# SCH_oscilliscope_copy_2021-08-04.net
KiCad netlist of a schematic drawn in EasyEDA
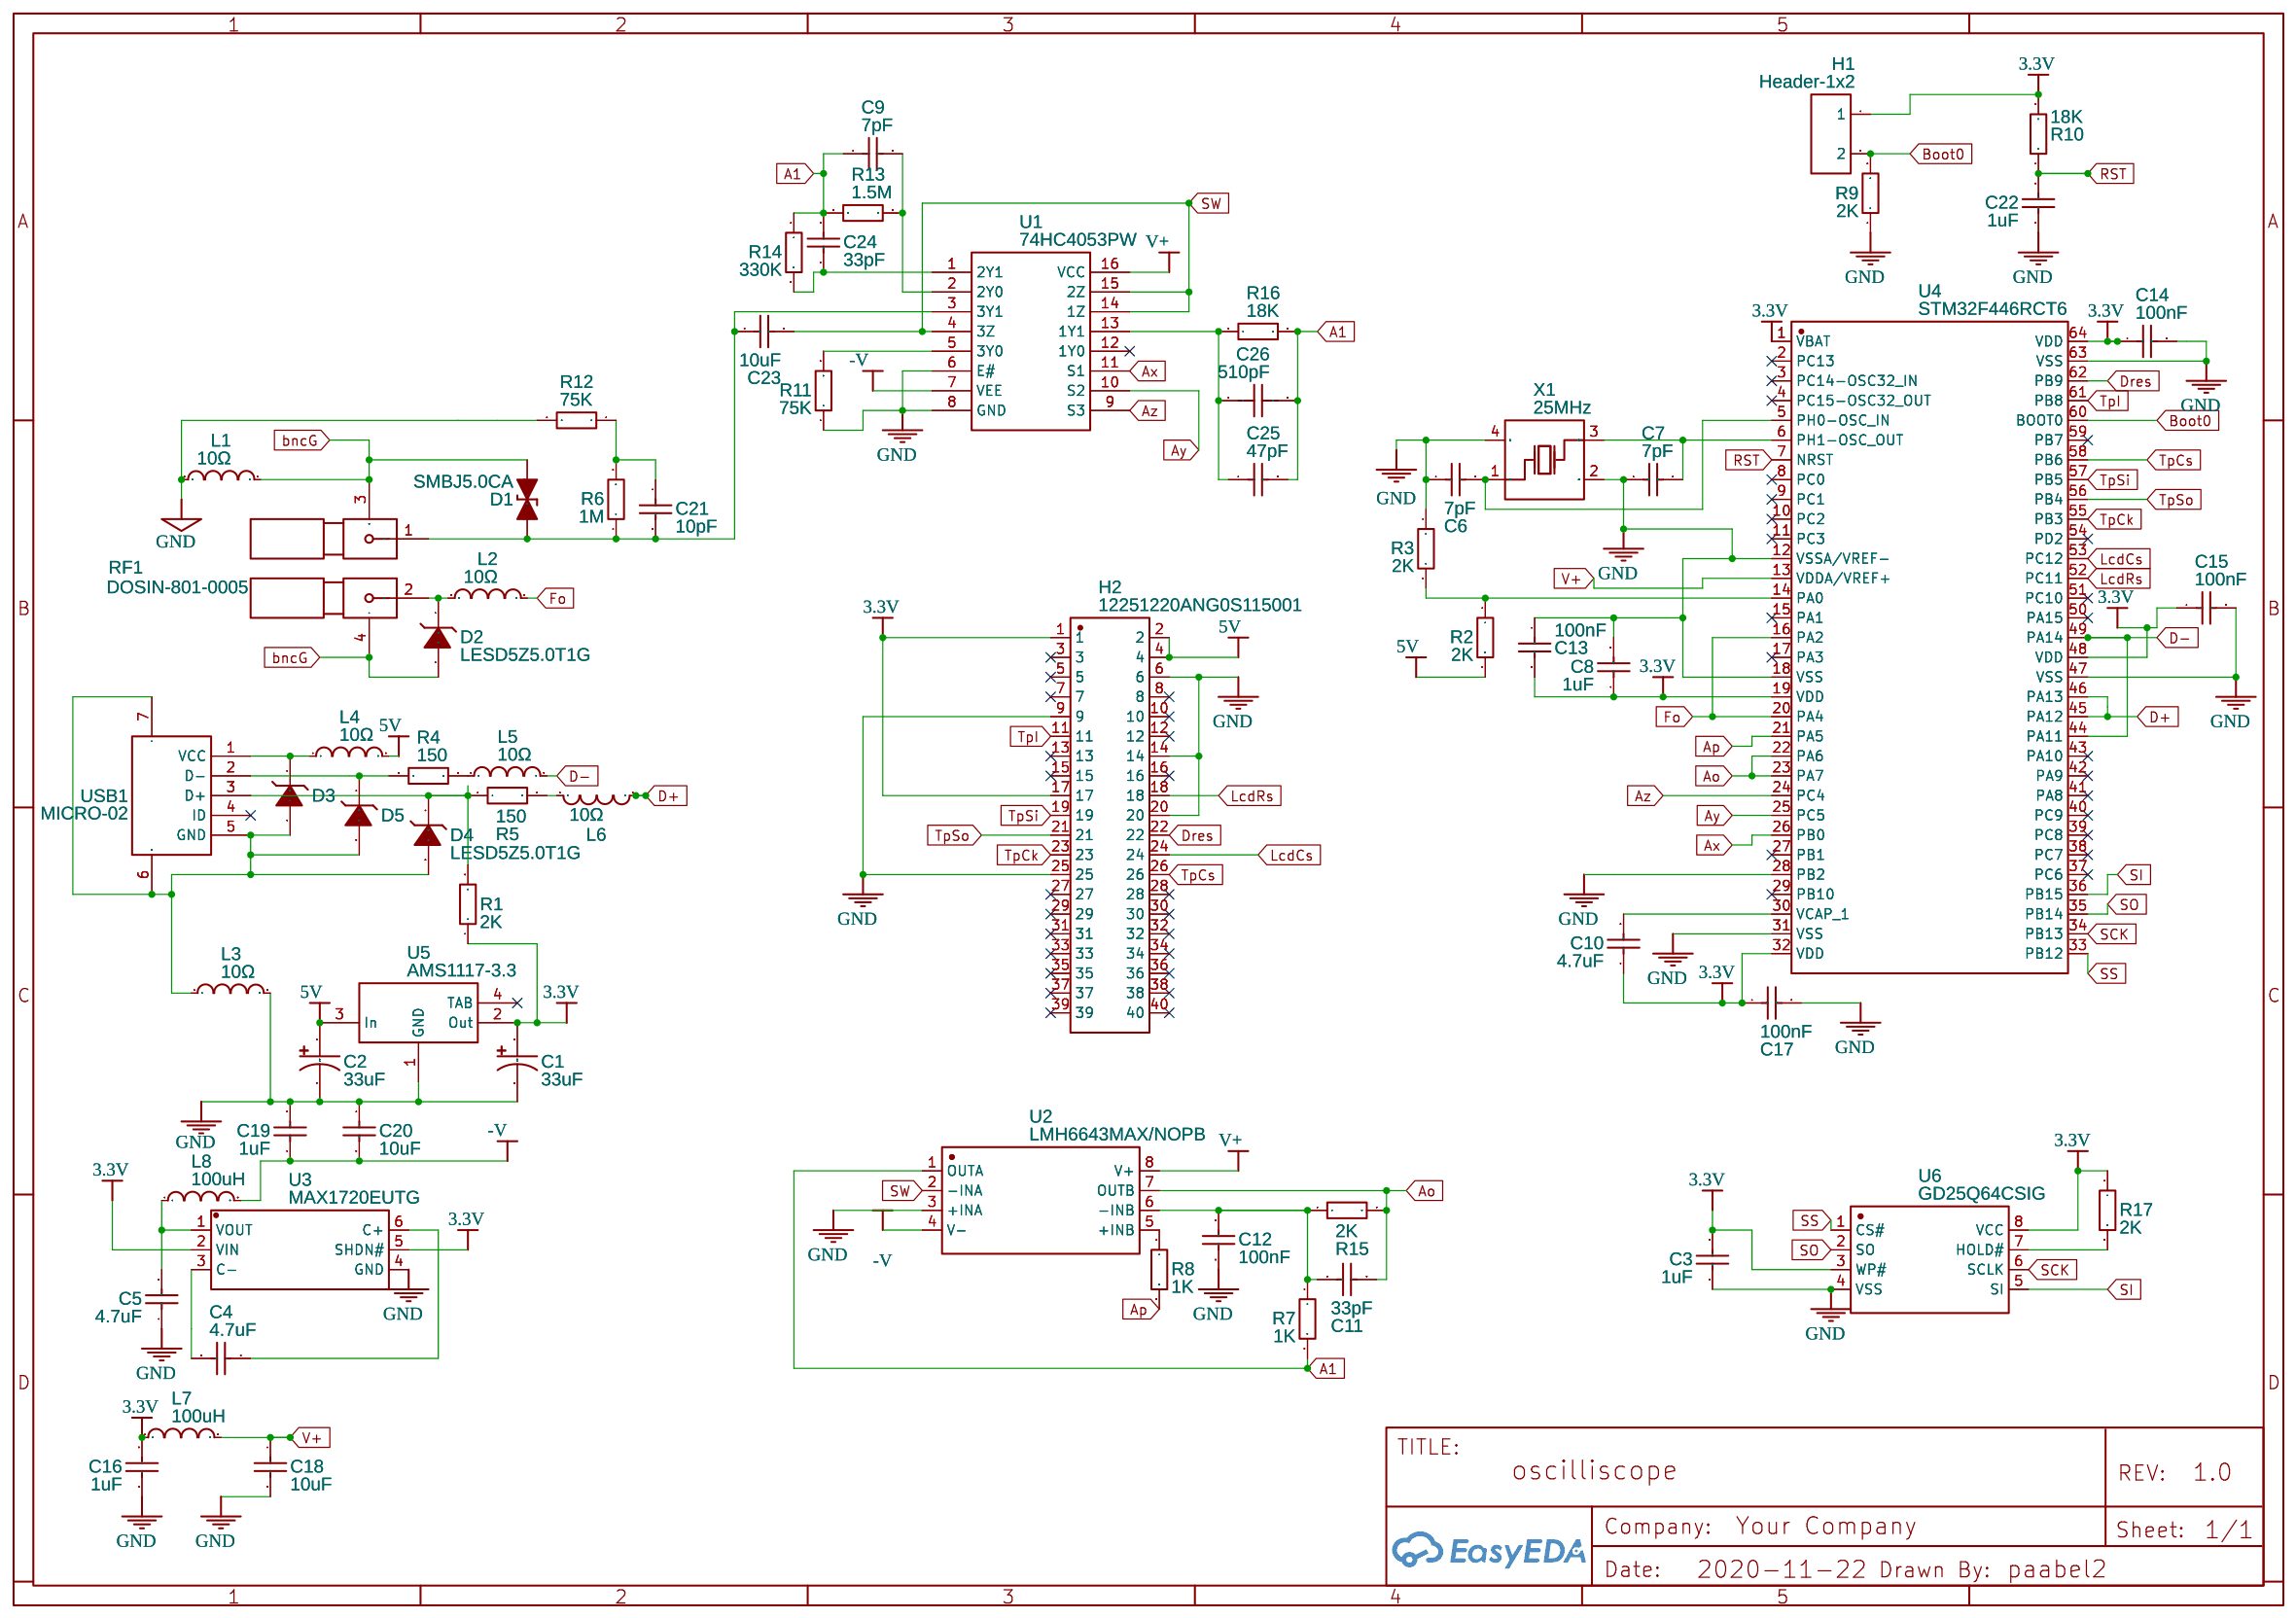
[diagram p0: schematic sheet]

(export (version "E")
  (design (tool "Eeschema 10.0.6"))
  (components
    (comp (ref "C1")
      (value "33uF")
      (fields
        (field (name "BOM_Manufacturer Part") "TC211A336M006Y")
        (field (name "BOM_Supplier Part") "C128344")
      )
      (libsource (lib "") (part "TC211A336M006Y"))
    )
    (comp (ref "C2")
      (value "33uF")
      (fields
        (field (name "BOM_Manufacturer Part") "TC211A336M006Y")
        (field (name "BOM_Supplier Part") "C128344")
      )
      (libsource (lib "") (part "TC211A336M006Y"))
    )
    (comp (ref "C3")
      (value "1uF")
      (fields
        (field (name "BOM_Manufacturer Part") "CL05A105KP5NNNC")
        (field (name "BOM_Supplier Part") "C14445")
      )
      (libsource (lib "") (part "CL05A105KP5NNNC"))
    )
    (comp (ref "C4")
      (value "4.7uF")
      (fields
        (field (name "BOM_Manufacturer Part") "CL21A475KAQNNNE")
        (field (name "BOM_Supplier Part") "C1779")
      )
      (libsource (lib "") (part "CL21A475KAQNNNE_1"))
    )
    (comp (ref "C5")
      (value "4.7uF")
      (fields
        (field (name "BOM_Manufacturer Part") "CL21A475KAQNNNE")
        (field (name "BOM_Supplier Part") "C1779")
      )
      (libsource (lib "") (part "CL21A475KAQNNNE"))
    )
    (comp (ref "C6")
      (value "7pF")
      (fields
        (field (name "BOM_Manufacturer Part") "0402CG7R0C500NT")
        (field (name "BOM_Supplier Part") "C1577")
      )
      (libsource (lib "") (part "0402CG7R0C500NT_1"))
    )
    (comp (ref "C7")
      (value "7pF")
      (fields
        (field (name "BOM_Manufacturer Part") "0402CG7R0C500NT")
        (field (name "BOM_Supplier Part") "C1577")
      )
      (libsource (lib "") (part "0402CG7R0C500NT"))
    )
    (comp (ref "C8")
      (value "1uF")
      (fields
        (field (name "BOM_Manufacturer Part") "CL05A105KP5NNNC")
        (field (name "BOM_Supplier Part") "C14445")
      )
      (libsource (lib "") (part "CL05A105KP5NNNC"))
    )
    (comp (ref "C9")
      (value "7pF")
      (fields
        (field (name "BOM_Manufacturer Part") "0402CG7R0C500NT")
        (field (name "BOM_Supplier Part") "C1577")
      )
      (libsource (lib "") (part "0402CG7R0C500NT"))
    )
    (comp (ref "C10")
      (value "4.7uF")
      (fields
        (field (name "BOM_Manufacturer Part") "CL21A475KAQNNNE")
        (field (name "BOM_Supplier Part") "C1779")
      )
      (libsource (lib "") (part "CL21A475KAQNNNE"))
    )
    (comp (ref "C11")
      (value "33pF")
      (fields
        (field (name "BOM_Manufacturer Part") "0402CG330J500NT")
        (field (name "BOM_Supplier Part") "C1562")
      )
      (libsource (lib "") (part "0402CG330J500NT"))
    )
    (comp (ref "C12")
      (value "100nF")
      (fields
        (field (name "BOM_Manufacturer Part") "CL05B104KO5NNNC")
        (field (name "BOM_Supplier Part") "C1525")
      )
      (libsource (lib "") (part "CL05B104KO5NNNC_1"))
    )
    (comp (ref "C13")
      (value "100nF")
      (fields
        (field (name "BOM_Manufacturer Part") "CL05B104KO5NNNC")
        (field (name "BOM_Supplier Part") "C1525")
      )
      (libsource (lib "") (part "CL05B104KO5NNNC_2"))
    )
    (comp (ref "C14")
      (value "100nF")
      (fields
        (field (name "BOM_Manufacturer Part") "CL05B104KO5NNNC")
        (field (name "BOM_Supplier Part") "C1525")
      )
      (libsource (lib "") (part "CL05B104KO5NNNC"))
    )
    (comp (ref "C15")
      (value "100nF")
      (fields
        (field (name "BOM_Manufacturer Part") "CL05B104KO5NNNC")
        (field (name "BOM_Supplier Part") "C1525")
      )
      (libsource (lib "") (part "CL05B104KO5NNNC"))
    )
    (comp (ref "C16")
      (value "1uF")
      (fields
        (field (name "BOM_Manufacturer Part") "CL05A105KP5NNNC")
        (field (name "BOM_Supplier Part") "C14445")
      )
      (libsource (lib "") (part "CL05A105KP5NNNC"))
    )
    (comp (ref "C17")
      (value "100nF")
      (fields
        (field (name "BOM_Manufacturer Part") "CL05B104KO5NNNC")
        (field (name "BOM_Supplier Part") "C1525")
      )
      (libsource (lib "") (part "CL05B104KO5NNNC_3"))
    )
    (comp (ref "C18")
      (value "10uF")
      (fields
        (field (name "BOM_Manufacturer Part") "CL21A106KAYNNNE")
        (field (name "BOM_Supplier Part") "C15850")
      )
      (libsource (lib "") (part "CL21A106KAYNNNE_1"))
    )
    (comp (ref "C19")
      (value "1uF")
      (fields
        (field (name "BOM_Manufacturer Part") "CL05A105KP5NNNC")
        (field (name "BOM_Supplier Part") "C14445")
      )
      (libsource (lib "") (part "CL05A105KP5NNNC"))
    )
    (comp (ref "C20")
      (value "10uF")
      (fields
        (field (name "BOM_Manufacturer Part") "CL21A106KAYNNNE")
        (field (name "BOM_Supplier Part") "C15850")
      )
      (libsource (lib "") (part "CL21A106KAYNNNE_1"))
    )
    (comp (ref "C21")
      (value "10pF")
      (fields
        (field (name "BOM_Manufacturer Part") "CL10C100JB8NNNC")
        (field (name "BOM_Supplier Part") "C1634")
      )
      (libsource (lib "") (part "CL10C100JB8NNNC"))
    )
    (comp (ref "C22")
      (value "1uF")
      (fields
        (field (name "BOM_Manufacturer Part") "CL05A105KP5NNNC")
        (field (name "BOM_Supplier Part") "C14445")
      )
      (libsource (lib "") (part "CL05A105KP5NNNC"))
    )
    (comp (ref "C23")
      (value "10uF")
      (fields
        (field (name "BOM_Manufacturer Part") "CL21A106KAYNNNE")
        (field (name "BOM_Supplier Part") "C15850")
      )
      (libsource (lib "") (part "CL21A106KAYNNNE"))
    )
    (comp (ref "C24")
      (value "33pF")
      (fields
        (field (name "BOM_Manufacturer Part") "0402CG330J500NT")
        (field (name "BOM_Supplier Part") "C1562")
      )
      (libsource (lib "") (part "0402CG330J500NT_1"))
    )
    (comp (ref "C25")
      (value "47pF")
      (fields
        (field (name "BOM_Manufacturer Part") "CL10C470JB8NNNC")
        (field (name "BOM_Supplier Part") "C1671")
      )
      (libsource (lib "") (part "CL10C470JB8NNNC"))
    )
    (comp (ref "C26")
      (value "510pF")
      (fields
        (field (name "BOM_Manufacturer Part") "CL10B511KB8NNNC")
        (field (name "BOM_Supplier Part") "C170144")
      )
      (libsource (lib "") (part "CL10B511KB8NNNC"))
    )
    (comp (ref "D1")
      (value "SMBJ5.0CA")
      (fields (field (name "BOM_Supplier Part") "C78424"))
      (libsource (lib "") (part "SMBJ5.0CA-C78424"))
    )
    (comp (ref "D2")
      (value "LESD5Z5.0T1G")
      (fields (field (name "BOM_Supplier Part") "C136171"))
      (libsource (lib "") (part "LESD5Z5.0T1G"))
    )
    (comp (ref "D3")
      (value "LESD5Z5.0T1G")
      (fields (field (name "BOM_Supplier Part") "C136171"))
      (libsource (lib "") (part "LESD5Z5.0T1G"))
    )
    (comp (ref "D4")
      (value "LESD5Z5.0T1G")
      (fields (field (name "BOM_Supplier Part") "C136171"))
      (libsource (lib "") (part "LESD5Z5.0T1G"))
    )
    (comp (ref "D5")
      (value "LESD5Z5.0T1G")
      (fields (field (name "BOM_Supplier Part") "C136171"))
      (libsource (lib "") (part "LESD5Z5.0T1G"))
    )
    (comp (ref "H1")
      (value "Header-1x2")
      (fields (field (name "BOM_Manufacturer Part") "826629-2") (field (name "BOM_Supplier Part") "C86471"))
      (libsource (lib "") (part "Header-Male-2.54_1x2"))
    )
    (comp (ref "H2")
      (value "12251220ANG0S115001")
      (fields (field (name "BOM_Supplier Part") "C429965"))
      (libsource (lib "") (part "12251220ANG0S115001"))
    )
    (comp (ref "L1")
      (value "10Ω")
      (fields
        (field (name "BOM_Manufacturer Part") "BLM15AG100SN1D")
        (field (name "BOM_Supplier Part") "C76882")
      )
      (libsource (lib "") (part "BLM15AG100SN1D_1"))
    )
    (comp (ref "L2")
      (value "10Ω")
      (fields
        (field (name "BOM_Manufacturer Part") "BLM15AG100SN1D")
        (field (name "BOM_Supplier Part") "C76882")
      )
      (libsource (lib "") (part "BLM15AG100SN1D_3"))
    )
    (comp (ref "L3")
      (value "10Ω")
      (fields
        (field (name "BOM_Manufacturer Part") "BLM15AG100SN1D")
        (field (name "BOM_Supplier Part") "C76882")
      )
      (libsource (lib "") (part "BLM15AG100SN1D_4"))
    )
    (comp (ref "L4")
      (value "10Ω")
      (fields
        (field (name "BOM_Manufacturer Part") "BLM15AG100SN1D")
        (field (name "BOM_Supplier Part") "C76882")
      )
      (libsource (lib "") (part "BLM15AG100SN1D_2"))
    )
    (comp (ref "L5")
      (value "10Ω")
      (fields
        (field (name "BOM_Manufacturer Part") "BLM15AG100SN1D")
        (field (name "BOM_Supplier Part") "C76882")
      )
      (libsource (lib "") (part "BLM15AG100SN1D_2"))
    )
    (comp (ref "L6")
      (value "10Ω")
      (fields
        (field (name "BOM_Manufacturer Part") "BLM15AG100SN1D")
        (field (name "BOM_Supplier Part") "C76882")
      )
      (libsource (lib "") (part "BLM15AG100SN1D"))
    )
    (comp (ref "L7")
      (value "100uH")
      (fields
        (field (name "BOM_Manufacturer Part") "SCCD32-101KT")
        (field (name "BOM_Supplier Part") "C532859")
      )
      (libsource (lib "") (part "SCCD32-101KT"))
    )
    (comp (ref "L8")
      (value "100uH")
      (fields
        (field (name "BOM_Manufacturer Part") "SCCD32-101KT")
        (field (name "BOM_Supplier Part") "C532859")
      )
      (libsource (lib "") (part "SCCD32-101KT"))
    )
    (comp (ref "R1")
      (value "2K")
      (fields
        (field (name "BOM_Manufacturer Part") "0603WAF2001T5E")
        (field (name "BOM_Supplier Part") "C22975")
      )
      (libsource (lib "") (part "0603WAF2001T5E_2"))
    )
    (comp (ref "R2")
      (value "2K")
      (fields
        (field (name "BOM_Manufacturer Part") "0603WAF2001T5E")
        (field (name "BOM_Supplier Part") "C22975")
      )
      (libsource (lib "") (part "0603WAF2001T5E_1"))
    )
    (comp (ref "R3")
      (value "2K")
      (fields
        (field (name "BOM_Manufacturer Part") "0603WAF2001T5E")
        (field (name "BOM_Supplier Part") "C22975")
      )
      (libsource (lib "") (part "0603WAF2001T5E_1"))
    )
    (comp (ref "R4")
      (value "150")
      (fields
        (field (name "BOM_Manufacturer Part") "0603WAF1500T5E")
        (field (name "BOM_Supplier Part") "C22808")
      )
      (libsource (lib "") (part "0603WAF1500T5E"))
    )
    (comp (ref "R5")
      (value "150")
      (fields
        (field (name "BOM_Manufacturer Part") "0603WAF1500T5E")
        (field (name "BOM_Supplier Part") "C22808")
      )
      (libsource (lib "") (part "0603WAF1500T5E"))
    )
    (comp (ref "R6")
      (value "1M")
      (fields
        (field (name "BOM_Manufacturer Part") "0603WAF1004T5E")
        (field (name "BOM_Supplier Part") "C22935")
      )
      (libsource (lib "") (part "0603WAF1004T5E"))
    )
    (comp (ref "R7")
      (value "1K")
      (fields
        (field (name "BOM_Manufacturer Part") "0603WAF1001T5E")
        (field (name "BOM_Supplier Part") "C21190")
      )
      (libsource (lib "") (part "0603WAF1001T5E"))
    )
    (comp (ref "R8")
      (value "1K")
      (fields
        (field (name "BOM_Manufacturer Part") "0603WAF1001T5E")
        (field (name "BOM_Supplier Part") "C21190")
      )
      (libsource (lib "") (part "0603WAF1001T5E"))
    )
    (comp (ref "R9")
      (value "2K")
      (fields
        (field (name "BOM_Manufacturer Part") "0603WAF2001T5E")
        (field (name "BOM_Supplier Part") "C22975")
      )
      (libsource (lib "") (part "0603WAF2001T5E_2"))
    )
    (comp (ref "R10")
      (value "18K")
      (fields
        (field (name "BOM_Manufacturer Part") "0603WAF1802T5E")
        (field (name "BOM_Supplier Part") "C25810")
      )
      (libsource (lib "") (part "0603WAF1802T5E"))
    )
    (comp (ref "R11")
      (value "75K")
      (fields
        (field (name "BOM_Manufacturer Part") "0603WAF7502T5E")
        (field (name "BOM_Supplier Part") "C23242")
      )
      (libsource (lib "") (part "0603WAF7502T5E"))
    )
    (comp (ref "R12")
      (value "75K")
      (fields
        (field (name "BOM_Manufacturer Part") "0603WAF7502T5E")
        (field (name "BOM_Supplier Part") "C23242")
      )
      (libsource (lib "") (part "0603WAF7502T5E_1"))
    )
    (comp (ref "R13")
      (value "1.5M")
      (fields
        (field (name "BOM_Manufacturer Part") "0603WAF1504T5E")
        (field (name "BOM_Supplier Part") "C4172")
      )
      (libsource (lib "") (part "0603WAF1504T5E"))
    )
    (comp (ref "R14")
      (value "330K")
      (fields
        (field (name "BOM_Manufacturer Part") "RTT03334JTP")
        (field (name "BOM_Supplier Part") "C103555")
      )
      (libsource (lib "") (part "RTT03334JTP"))
    )
    (comp (ref "R15")
      (value "2K")
      (fields
        (field (name "BOM_Manufacturer Part") "0603WAF2001T5E")
        (field (name "BOM_Supplier Part") "C22975")
      )
      (libsource (lib "") (part "0603WAF2001T5E"))
    )
    (comp (ref "R16")
      (value "18K")
      (fields
        (field (name "BOM_Manufacturer Part") "0603WAF1802T5E")
        (field (name "BOM_Supplier Part") "C25810")
      )
      (libsource (lib "") (part "0603WAF1802T5E_1"))
    )
    (comp (ref "R17")
      (value "2K")
      (fields
        (field (name "BOM_Manufacturer Part") "0603WAF2001T5E")
        (field (name "BOM_Supplier Part") "C22975")
      )
      (libsource (lib "") (part "0603WAF2001T5E_1"))
    )
    (comp (ref "RF1")
      (value "DOSIN-801-0005")
      (fields (field (name "BOM_Supplier Part") "C521213"))
      (libsource (lib "") (part "DOSIN-801-0005"))
    )
    (comp (ref "U1")
      (value "74HC4053PW")
      (fields (field (name "BOM_Supplier Part") "C5648"))
      (libsource (lib "") (part "74HC4053PW"))
    )
    (comp (ref "U2")
      (value "LMH6643MAX/NOPB")
      (fields (field (name "BOM_Supplier Part") "C44880"))
      (libsource (lib "") (part "LMH6643MAX/NOPB"))
    )
    (comp (ref "U3")
      (value "MAX1720EUTG")
      (fields (field (name "BOM_Supplier Part") "C70466"))
      (libsource (lib "") (part "MAX1720EUTG"))
    )
    (comp (ref "U4")
      (value "STM32F446RCT6")
      (fields (field (name "BOM_Supplier Part") "C1338449"))
      (libsource (lib "") (part "STM32F446RET6"))
    )
    (comp (ref "U5")
      (value "AMS1117-3.3")
      (fields (field (name "BOM_Supplier Part") "C165482"))
      (libsource (lib "") (part "AMS1117-3.3_C165482"))
    )
    (comp (ref "U6")
      (value "GD25Q64CSIG")
      (fields (field (name "BOM_Supplier Part") "C79076"))
      (libsource (lib "") (part "GD25Q64CSIG"))
    )
    (comp (ref "USB1")
      (value "MICRO-02")
      (fields
        (field (name "BOM_Manufacturer Part") "MICRO-02-G1P3-A1T2")
        (field (name "BOM_Supplier Part") "C2682518")
      )
      (libsource (lib "") (part "MICRO-02-G1P3-A1T2"))
    )
    (comp (ref "X1")
      (value "25MHz")
      (fields
        (field (name "BOM_Manufacturer Part") "X322525MOB4SI")
        (field (name "BOM_Supplier Part") "C9006")
      )
      (libsource (lib "") (part "X322525MOB4SI"))
    )
  )
  (nets
    (net (code "1") (name "-V") (class "Default")
      (node (ref "C19") (pin "1") (pinfunction "1_1") (pintype "input"))
      (node (ref "C20") (pin "2") (pinfunction "2_2") (pintype "input"))
      (node (ref "L8") (pin "2") (pinfunction "2_2") (pintype "unspecified"))
      (node (ref "U1") (pin "7") (pinfunction "VEE_7") (pintype "unspecified"))
      (node (ref "U2") (pin "4") (pinfunction "V-_4") (pintype "unspecified"))
    )
    (net (code "2") (name "3.3V") (class "Default")
      (node (ref "C1") (pin "1") (pinfunction "1_1") (pintype "unspecified"))
      (node (ref "C10") (pin "1") (pinfunction "1_1") (pintype "input"))
      (node (ref "C13") (pin "2") (pinfunction "2_2") (pintype "input"))
      (node (ref "C14") (pin "1") (pinfunction "1_1") (pintype "input"))
      (node (ref "C15") (pin "1") (pinfunction "1_1") (pintype "input"))
      (node (ref "C16") (pin "2") (pinfunction "2_2") (pintype "input"))
      (node (ref "C17") (pin "1") (pinfunction "1_1") (pintype "input"))
      (node (ref "C3") (pin "2") (pinfunction "2_2") (pintype "input"))
      (node (ref "C8") (pin "1") (pinfunction "1_1") (pintype "input"))
      (node (ref "H1") (pin "1") (pinfunction "1_1") (pintype "unspecified"))
      (node (ref "H2") (pin "1") (pinfunction "1_1") (pintype "unspecified"))
      (node (ref "H2") (pin "17") (pinfunction "17_17") (pintype "unspecified"))
      (node (ref "L7") (pin "1") (pinfunction "1_1") (pintype "unspecified"))
      (node (ref "R1") (pin "1") (pinfunction "1_1") (pintype "input"))
      (node (ref "R10") (pin "2") (pinfunction "2_2") (pintype "input"))
      (node (ref "R17") (pin "1") (pinfunction "1_1") (pintype "input"))
      (node (ref "U3") (pin "2") (pinfunction "VIN_2") (pintype "unspecified"))
      (node (ref "U3") (pin "5") (pinfunction "SHDN#_5") (pintype "unspecified"))
      (node (ref "U4") (pin "1") (pinfunction "VBAT_1") (pintype "unspecified"))
      (node (ref "U4") (pin "19") (pinfunction "VDD_19") (pintype "unspecified"))
      (node (ref "U4") (pin "32") (pinfunction "VDD_32") (pintype "unspecified"))
      (node (ref "U4") (pin "48") (pinfunction "VDD_48") (pintype "unspecified"))
      (node (ref "U4") (pin "64") (pinfunction "VDD_64") (pintype "unspecified"))
      (node (ref "U5") (pin "2") (pinfunction "Out_2") (pintype "unspecified"))
      (node (ref "U6") (pin "3") (pinfunction "WP#_3") (pintype "unspecified"))
      (node (ref "U6") (pin "8") (pinfunction "VCC_8") (pintype "unspecified"))
    )
    (net (code "3") (name "5V") (class "Default")
      (node (ref "C2") (pin "1") (pinfunction "1_1") (pintype "unspecified"))
      (node (ref "H2") (pin "2") (pinfunction "2_2") (pintype "unspecified"))
      (node (ref "H2") (pin "4") (pinfunction "4_4") (pintype "unspecified"))
      (node (ref "L4") (pin "2") (pinfunction "2_2") (pintype "unspecified"))
      (node (ref "R2") (pin "2") (pinfunction "2_2") (pintype "input"))
      (node (ref "U5") (pin "3") (pinfunction "In_3") (pintype "unspecified"))
    )
    (net (code "4") (name "A1") (class "Default")
      (node (ref "C24") (pin "2") (pinfunction "2_2") (pintype "input"))
      (node (ref "C25") (pin "2") (pinfunction "2_2") (pintype "input"))
      (node (ref "C26") (pin "2") (pinfunction "2_2") (pintype "unspecified"))
      (node (ref "C9") (pin "1") (pinfunction "1_1") (pintype "input"))
      (node (ref "R13") (pin "1") (pinfunction "1_1") (pintype "input"))
      (node (ref "R14") (pin "1") (pinfunction "1_1") (pintype "input"))
      (node (ref "R16") (pin "2") (pinfunction "2_2") (pintype "input"))
      (node (ref "R7") (pin "2") (pinfunction "2_2") (pintype "input"))
      (node (ref "U2") (pin "1") (pinfunction "OUTA_1") (pintype "unspecified"))
    )
    (net (code "5") (name "Ao") (class "Default")
      (node (ref "C11") (pin "2") (pinfunction "2_2") (pintype "input"))
      (node (ref "R15") (pin "2") (pinfunction "2_2") (pintype "input"))
      (node (ref "U2") (pin "7") (pinfunction "OUTB_7") (pintype "unspecified"))
      (node (ref "U4") (pin "22") (pinfunction "PA6_22") (pintype "unspecified"))
      (node (ref "U4") (pin "23") (pinfunction "PA7_23") (pintype "unspecified"))
    )
    (net (code "6") (name "Ap") (class "Default")
      (node (ref "R8") (pin "2") (pinfunction "2_2") (pintype "input"))
      (node (ref "U4") (pin "21") (pinfunction "PA5_21") (pintype "unspecified"))
    )
    (net (code "7") (name "Ax") (class "Default")
      (node (ref "U1") (pin "11") (pinfunction "S1_11") (pintype "unspecified"))
      (node (ref "U4") (pin "26") (pinfunction "PB0_26") (pintype "unspecified"))
    )
    (net (code "8") (name "Ay") (class "Default")
      (node (ref "U1") (pin "10") (pinfunction "S2_10") (pintype "unspecified"))
      (node (ref "U4") (pin "25") (pinfunction "PC5_25") (pintype "unspecified"))
    )
    (net (code "9") (name "Az") (class "Default")
      (node (ref "U1") (pin "9") (pinfunction "S3_9") (pintype "unspecified"))
      (node (ref "U4") (pin "24") (pinfunction "PC4_24") (pintype "unspecified"))
    )
    (net (code "10") (name "Boot0") (class "Default")
      (node (ref "H1") (pin "2") (pinfunction "2_2") (pintype "unspecified"))
      (node (ref "R9") (pin "2") (pinfunction "2_2") (pintype "input"))
      (node (ref "U4") (pin "60") (pinfunction "BOOT0_60") (pintype "unspecified"))
    )
    (net (code "11") (name "D+") (class "Default")
      (node (ref "L6") (pin "1") (pinfunction "1_1") (pintype "unspecified"))
      (node (ref "U4") (pin "45") (pinfunction "PA12_45") (pintype "unspecified"))
      (node (ref "U4") (pin "46") (pinfunction "PA13_46") (pintype "unspecified"))
    )
    (net (code "12") (name "D-") (class "Default")
      (node (ref "L5") (pin "2") (pinfunction "2_2") (pintype "unspecified"))
      (node (ref "U4") (pin "44") (pinfunction "PA11_44") (pintype "unspecified"))
      (node (ref "U4") (pin "49") (pinfunction "PA14_49") (pintype "unspecified"))
    )
    (net (code "13") (name "Dres") (class "Default")
      (node (ref "H2") (pin "22") (pinfunction "22_22") (pintype "unspecified"))
      (node (ref "U4") (pin "62") (pinfunction "PB9_62") (pintype "unspecified"))
    )
    (net (code "14") (name "Fo") (class "Default")
      (node (ref "L2") (pin "1") (pinfunction "1_1") (pintype "unspecified"))
      (node (ref "U4") (pin "16") (pinfunction "PA2_16") (pintype "unspecified"))
      (node (ref "U4") (pin "20") (pinfunction "PA4_20") (pintype "unspecified"))
    )
    (net (code "15") (name "GND") (class "Default")
      (node (ref "C1") (pin "2") (pinfunction "2_2") (pintype "unspecified"))
      (node (ref "C12") (pin "2") (pinfunction "2_2") (pintype "input"))
      (node (ref "C13") (pin "1") (pinfunction "1_1") (pintype "input"))
      (node (ref "C14") (pin "2") (pinfunction "2_2") (pintype "input"))
      (node (ref "C15") (pin "2") (pinfunction "2_2") (pintype "input"))
      (node (ref "C16") (pin "1") (pinfunction "1_1") (pintype "input"))
      (node (ref "C17") (pin "2") (pinfunction "2_2") (pintype "input"))
      (node (ref "C18") (pin "2") (pinfunction "2_2") (pintype "input"))
      (node (ref "C19") (pin "2") (pinfunction "2_2") (pintype "input"))
      (node (ref "C2") (pin "2") (pinfunction "2_2") (pintype "unspecified"))
      (node (ref "C20") (pin "1") (pinfunction "1_1") (pintype "input"))
      (node (ref "C22") (pin "1") (pinfunction "1_1") (pintype "input"))
      (node (ref "C3") (pin "1") (pinfunction "1_1") (pintype "input"))
      (node (ref "C5") (pin "1") (pinfunction "1_1") (pintype "input"))
      (node (ref "C6") (pin "1") (pinfunction "1_1") (pintype "input"))
      (node (ref "C7") (pin "1") (pinfunction "1_1") (pintype "input"))
      (node (ref "C8") (pin "2") (pinfunction "2_2") (pintype "input"))
      (node (ref "H2") (pin "14") (pinfunction "14_14") (pintype "unspecified"))
      (node (ref "H2") (pin "20") (pinfunction "20_20") (pintype "unspecified"))
      (node (ref "H2") (pin "25") (pinfunction "25_25") (pintype "unspecified"))
      (node (ref "H2") (pin "6") (pinfunction "6_6") (pintype "unspecified"))
      (node (ref "H2") (pin "9") (pinfunction "9_9") (pintype "unspecified"))
      (node (ref "L1") (pin "2") (pinfunction "2_2") (pintype "unspecified"))
      (node (ref "L3") (pin "2") (pinfunction "2_2") (pintype "unspecified"))
      (node (ref "R11") (pin "1") (pinfunction "1_1") (pintype "input"))
      (node (ref "R12") (pin "2") (pinfunction "2_2") (pintype "input"))
      (node (ref "R3") (pin "1") (pinfunction "1_1") (pintype "input"))
      (node (ref "R9") (pin "1") (pinfunction "1_1") (pintype "input"))
      (node (ref "U1") (pin "6") (pinfunction "E#_6") (pintype "unspecified"))
      (node (ref "U1") (pin "8") (pinfunction "GND_8") (pintype "unspecified"))
      (node (ref "U2") (pin "3") (pinfunction "+INA_3") (pintype "unspecified"))
      (node (ref "U3") (pin "4") (pinfunction "GND_4") (pintype "unspecified"))
      (node (ref "U4") (pin "12") (pinfunction "VSSA/VREF-_12") (pintype "unspecified"))
      (node (ref "U4") (pin "18") (pinfunction "VSS_18") (pintype "unspecified"))
      (node (ref "U4") (pin "28") (pinfunction "PB2_28") (pintype "unspecified"))
      (node (ref "U4") (pin "31") (pinfunction "VSS_31") (pintype "unspecified"))
      (node (ref "U4") (pin "47") (pinfunction "VSS_47") (pintype "unspecified"))
      (node (ref "U4") (pin "63") (pinfunction "VSS_63") (pintype "unspecified"))
      (node (ref "U5") (pin "1") (pinfunction "GND_1") (pintype "unspecified"))
      (node (ref "U6") (pin "4") (pinfunction "VSS_4") (pintype "unspecified"))
      (node (ref "X1") (pin "2") (pinfunction "GND_2") (pintype "unspecified"))
      (node (ref "X1") (pin "4") (pinfunction "GND_4") (pintype "unspecified"))
    )
    (net (code "16") (name "LcdCs") (class "Default")
      (node (ref "H2") (pin "24") (pinfunction "24_24") (pintype "unspecified"))
      (node (ref "U4") (pin "53") (pinfunction "PC12_53") (pintype "unspecified"))
    )
    (net (code "17") (name "LcdRs") (class "Default")
      (node (ref "H2") (pin "18") (pinfunction "18_18") (pintype "unspecified"))
      (node (ref "U4") (pin "52") (pinfunction "PC11_52") (pintype "unspecified"))
    )
    (net (code "18") (name "Net-(C21-Pad1)") (class "Default")
      (node (ref "C21") (pin "1") (pinfunction "1_1") (pintype "input"))
      (node (ref "R12") (pin "1") (pinfunction "1_1") (pintype "input"))
      (node (ref "R6") (pin "2") (pinfunction "2_2") (pintype "input"))
    )
    (net (code "19") (name "Net-(D2-C)") (class "Default")
      (node (ref "D2") (pin "1") (pinfunction "C_1") (pintype "unspecified"))
      (node (ref "L2") (pin "2") (pinfunction "2_2") (pintype "unspecified"))
      (node (ref "RF1") (pin "2") (pinfunction "2_2") (pintype "unspecified"))
    )
    (net (code "20") (name "Net-(D3-A)") (class "Default")
      (node (ref "D3") (pin "2") (pinfunction "A_2") (pintype "unspecified"))
      (node (ref "D4") (pin "2") (pinfunction "A_2") (pintype "unspecified"))
      (node (ref "D5") (pin "2") (pinfunction "A_2") (pintype "unspecified"))
      (node (ref "L3") (pin "1") (pinfunction "1_1") (pintype "unspecified"))
      (node (ref "USB1") (pin "5") (pinfunction "GND_5") (pintype "input"))
      (node (ref "USB1") (pin "6") (pinfunction "6_6") (pintype "input"))
      (node (ref "USB1") (pin "7") (pinfunction "7_7") (pintype "input"))
    )
    (net (code "21") (name "Net-(D3-C)") (class "Default")
      (node (ref "D3") (pin "1") (pinfunction "C_1") (pintype "unspecified"))
      (node (ref "L4") (pin "1") (pinfunction "1_1") (pintype "unspecified"))
      (node (ref "USB1") (pin "1") (pinfunction "VCC_1") (pintype "input"))
    )
    (net (code "22") (name "Net-(D4-C)") (class "Default")
      (node (ref "D4") (pin "1") (pinfunction "C_1") (pintype "unspecified"))
      (node (ref "R1") (pin "2") (pinfunction "2_2") (pintype "input"))
      (node (ref "R5") (pin "1") (pinfunction "1_1") (pintype "input"))
      (node (ref "USB1") (pin "3") (pinfunction "D+_3") (pintype "input"))
    )
    (net (code "23") (name "Net-(D5-C)") (class "Default")
      (node (ref "D5") (pin "1") (pinfunction "C_1") (pintype "unspecified"))
      (node (ref "R4") (pin "1") (pinfunction "1_1") (pintype "input"))
      (node (ref "USB1") (pin "2") (pinfunction "D-_2") (pintype "input"))
    )
    (net (code "24") (name "Net-(L5-Pad1)") (class "Default")
      (node (ref "L5") (pin "1") (pinfunction "1_1") (pintype "unspecified"))
      (node (ref "R4") (pin "2") (pinfunction "2_2") (pintype "input"))
    )
    (net (code "25") (name "Net-(L6-Pad2)") (class "Default")
      (node (ref "L6") (pin "2") (pinfunction "2_2") (pintype "unspecified"))
      (node (ref "R5") (pin "2") (pinfunction "2_2") (pintype "input"))
    )
    (net (code "26") (name "Net-(U1-1Y1)") (class "Default")
      (node (ref "C25") (pin "1") (pinfunction "1_1") (pintype "input"))
      (node (ref "C26") (pin "1") (pinfunction "1_1") (pintype "unspecified"))
      (node (ref "R16") (pin "1") (pinfunction "1_1") (pintype "input"))
      (node (ref "U1") (pin "13") (pinfunction "1Y1_13") (pintype "unspecified"))
    )
    (net (code "27") (name "Net-(U1-2Y0)") (class "Default")
      (node (ref "C9") (pin "2") (pinfunction "2_2") (pintype "input"))
      (node (ref "R13") (pin "2") (pinfunction "2_2") (pintype "input"))
      (node (ref "U1") (pin "2") (pinfunction "2Y0_2") (pintype "unspecified"))
    )
    (net (code "28") (name "Net-(U1-2Y1)") (class "Default")
      (node (ref "C24") (pin "1") (pinfunction "1_1") (pintype "input"))
      (node (ref "R14") (pin "2") (pinfunction "2_2") (pintype "input"))
      (node (ref "U1") (pin "1") (pinfunction "2Y1_1") (pintype "unspecified"))
    )
    (net (code "29") (name "Net-(U1-3Y0)") (class "Default")
      (node (ref "R11") (pin "2") (pinfunction "2_2") (pintype "input"))
      (node (ref "U1") (pin "5") (pinfunction "3Y0_5") (pintype "unspecified"))
    )
    (net (code "30") (name "Net-(U1-3Y1)") (class "Default")
      (node (ref "C21") (pin "2") (pinfunction "2_2") (pintype "input"))
      (node (ref "C23") (pin "2") (pinfunction "2_2") (pintype "input"))
      (node (ref "D1") (pin "1") (pinfunction "1_1") (pintype "unspecified"))
      (node (ref "R6") (pin "1") (pinfunction "1_1") (pintype "input"))
      (node (ref "RF1") (pin "1") (pinfunction "1_1") (pintype "unspecified"))
      (node (ref "U1") (pin "3") (pinfunction "3Y1_3") (pintype "unspecified"))
    )
    (net (code "31") (name "Net-(U2-+INB)") (class "Default")
      (node (ref "R8") (pin "1") (pinfunction "1_1") (pintype "input"))
      (node (ref "U2") (pin "5") (pinfunction "+INB_5") (pintype "unspecified"))
    )
    (net (code "32") (name "Net-(U2--INB)") (class "Default")
      (node (ref "C11") (pin "1") (pinfunction "1_1") (pintype "input"))
      (node (ref "C12") (pin "1") (pinfunction "1_1") (pintype "input"))
      (node (ref "R15") (pin "1") (pinfunction "1_1") (pintype "input"))
      (node (ref "R7") (pin "1") (pinfunction "1_1") (pintype "input"))
      (node (ref "U2") (pin "6") (pinfunction "-INB_6") (pintype "unspecified"))
    )
    (net (code "33") (name "Net-(U3-C+)") (class "Default")
      (node (ref "C4") (pin "2") (pinfunction "2_2") (pintype "input"))
      (node (ref "U3") (pin "6") (pinfunction "C+_6") (pintype "unspecified"))
    )
    (net (code "34") (name "Net-(U3-C-)") (class "Default")
      (node (ref "C4") (pin "1") (pinfunction "1_1") (pintype "input"))
      (node (ref "U3") (pin "3") (pinfunction "C-_3") (pintype "unspecified"))
    )
    (net (code "35") (name "Net-(U3-VOUT)") (class "Default")
      (node (ref "C5") (pin "2") (pinfunction "2_2") (pintype "input"))
      (node (ref "L8") (pin "1") (pinfunction "1_1") (pintype "unspecified"))
      (node (ref "U3") (pin "1") (pinfunction "VOUT_1") (pintype "unspecified"))
    )
    (net (code "36") (name "Net-(U4-PA0)") (class "Default")
      (node (ref "R2") (pin "1") (pinfunction "1_1") (pintype "input"))
      (node (ref "R3") (pin "2") (pinfunction "2_2") (pintype "input"))
      (node (ref "U4") (pin "14") (pinfunction "PA0_14") (pintype "unspecified"))
    )
    (net (code "37") (name "Net-(U4-PH0-OSC_IN)") (class "Default")
      (node (ref "C6") (pin "2") (pinfunction "2_2") (pintype "input"))
      (node (ref "U4") (pin "5") (pinfunction "PH0-OSC_IN_5") (pintype "unspecified"))
      (node (ref "X1") (pin "1") (pinfunction "OSC1_1") (pintype "unspecified"))
    )
    (net (code "38") (name "Net-(U4-PH1-OSC_OUT)") (class "Default")
      (node (ref "C7") (pin "2") (pinfunction "2_2") (pintype "input"))
      (node (ref "U4") (pin "6") (pinfunction "PH1-OSC_OUT_6") (pintype "unspecified"))
      (node (ref "X1") (pin "3") (pinfunction "OSC2_3") (pintype "unspecified"))
    )
    (net (code "39") (name "Net-(U4-VCAP_1)") (class "Default")
      (node (ref "C10") (pin "2") (pinfunction "2_2") (pintype "input"))
      (node (ref "U4") (pin "30") (pinfunction "VCAP_1_30") (pintype "unspecified"))
    )
    (net (code "40") (name "Net-(U6-HOLD#)") (class "Default")
      (node (ref "R17") (pin "2") (pinfunction "2_2") (pintype "input"))
      (node (ref "U6") (pin "7") (pinfunction "HOLD#_7") (pintype "unspecified"))
    )
    (net (code "41") (name "RST") (class "Default")
      (node (ref "C22") (pin "2") (pinfunction "2_2") (pintype "input"))
      (node (ref "R10") (pin "1") (pinfunction "1_1") (pintype "input"))
      (node (ref "U4") (pin "7") (pinfunction "NRST_7") (pintype "unspecified"))
    )
    (net (code "42") (name "SCK") (class "Default")
      (node (ref "U4") (pin "34") (pinfunction "PB13_34") (pintype "unspecified"))
      (node (ref "U6") (pin "6") (pinfunction "SCLK_6") (pintype "unspecified"))
    )
    (net (code "43") (name "SI") (class "Default")
      (node (ref "U4") (pin "36") (pinfunction "PB15_36") (pintype "unspecified"))
      (node (ref "U6") (pin "5") (pinfunction "SI_5") (pintype "unspecified"))
    )
    (net (code "44") (name "SO") (class "Default")
      (node (ref "U4") (pin "35") (pinfunction "PB14_35") (pintype "unspecified"))
      (node (ref "U6") (pin "2") (pinfunction "SO_2") (pintype "unspecified"))
    )
    (net (code "45") (name "SS") (class "Default")
      (node (ref "U4") (pin "33") (pinfunction "PB12_33") (pintype "unspecified"))
      (node (ref "U6") (pin "1") (pinfunction "CS#_1") (pintype "unspecified"))
    )
    (net (code "46") (name "SW") (class "Default")
      (node (ref "C23") (pin "1") (pinfunction "1_1") (pintype "input"))
      (node (ref "U1") (pin "14") (pinfunction "1Z_14") (pintype "unspecified"))
      (node (ref "U1") (pin "15") (pinfunction "2Z_15") (pintype "unspecified"))
      (node (ref "U1") (pin "4") (pinfunction "3Z_4") (pintype "unspecified"))
      (node (ref "U2") (pin "2") (pinfunction "-INA_2") (pintype "unspecified"))
    )
    (net (code "47") (name "TpCk") (class "Default")
      (node (ref "H2") (pin "23") (pinfunction "23_23") (pintype "unspecified"))
      (node (ref "U4") (pin "55") (pinfunction "PB3_55") (pintype "unspecified"))
    )
    (net (code "48") (name "TpCs") (class "Default")
      (node (ref "H2") (pin "26") (pinfunction "26_26") (pintype "unspecified"))
      (node (ref "U4") (pin "58") (pinfunction "PB6_58") (pintype "unspecified"))
    )
    (net (code "49") (name "TpI") (class "Default")
      (node (ref "H2") (pin "11") (pinfunction "11_11") (pintype "unspecified"))
      (node (ref "U4") (pin "61") (pinfunction "PB8_61") (pintype "unspecified"))
    )
    (net (code "50") (name "TpSi") (class "Default")
      (node (ref "H2") (pin "19") (pinfunction "19_19") (pintype "unspecified"))
      (node (ref "U4") (pin "57") (pinfunction "PB5_57") (pintype "unspecified"))
    )
    (net (code "51") (name "TpSo") (class "Default")
      (node (ref "H2") (pin "21") (pinfunction "21_21") (pintype "unspecified"))
      (node (ref "U4") (pin "56") (pinfunction "PB4_56") (pintype "unspecified"))
    )
    (net (code "52") (name "V+") (class "Default")
      (node (ref "C18") (pin "1") (pinfunction "1_1") (pintype "input"))
      (node (ref "L7") (pin "2") (pinfunction "2_2") (pintype "unspecified"))
      (node (ref "U1") (pin "16") (pinfunction "VCC_16") (pintype "unspecified"))
      (node (ref "U2") (pin "8") (pinfunction "V+_8") (pintype "unspecified"))
      (node (ref "U4") (pin "13") (pinfunction "VDDA/VREF+_13") (pintype "unspecified"))
    )
    (net (code "53") (name "bncG") (class "Default")
      (node (ref "D1") (pin "2") (pinfunction "2_2") (pintype "unspecified"))
      (node (ref "D2") (pin "2") (pinfunction "A_2") (pintype "unspecified"))
      (node (ref "L1") (pin "1") (pinfunction "1_1") (pintype "unspecified"))
      (node (ref "RF1") (pin "3") (pinfunction "3_3") (pintype "unspecified"))
      (node (ref "RF1") (pin "4") (pinfunction "4_4") (pintype "unspecified"))
    )
    (net (code "54") (name "unconnected-(H2-Pad3)") (class "Default")
      (node (ref "H2") (pin "3") (pinfunction "3_3") (pintype "unspecified+no_connect"))
    )
    (net (code "55") (name "unconnected-(H2-Pad5)") (class "Default")
      (node (ref "H2") (pin "5") (pinfunction "5_5") (pintype "unspecified+no_connect"))
    )
    (net (code "56") (name "unconnected-(H2-Pad7)") (class "Default")
      (node (ref "H2") (pin "7") (pinfunction "7_7") (pintype "unspecified+no_connect"))
    )
    (net (code "57") (name "unconnected-(H2-Pad8)") (class "Default")
      (node (ref "H2") (pin "8") (pinfunction "8_8") (pintype "unspecified+no_connect"))
    )
    (net (code "58") (name "unconnected-(H2-Pad10)") (class "Default")
      (node (ref "H2") (pin "10") (pinfunction "10_10") (pintype "unspecified+no_connect"))
    )
    (net (code "59") (name "unconnected-(H2-Pad12)") (class "Default")
      (node (ref "H2") (pin "12") (pinfunction "12_12") (pintype "unspecified+no_connect"))
    )
    (net (code "60") (name "unconnected-(H2-Pad13)") (class "Default")
      (node (ref "H2") (pin "13") (pinfunction "13_13") (pintype "unspecified+no_connect"))
    )
    (net (code "61") (name "unconnected-(H2-Pad15)") (class "Default")
      (node (ref "H2") (pin "15") (pinfunction "15_15") (pintype "unspecified+no_connect"))
    )
    (net (code "62") (name "unconnected-(H2-Pad16)") (class "Default")
      (node (ref "H2") (pin "16") (pinfunction "16_16") (pintype "unspecified+no_connect"))
    )
    (net (code "63") (name "unconnected-(H2-Pad27)") (class "Default")
      (node (ref "H2") (pin "27") (pinfunction "27_27") (pintype "unspecified+no_connect"))
    )
    (net (code "64") (name "unconnected-(H2-Pad28)") (class "Default")
      (node (ref "H2") (pin "28") (pinfunction "28_28") (pintype "unspecified+no_connect"))
    )
    (net (code "65") (name "unconnected-(H2-Pad29)") (class "Default")
      (node (ref "H2") (pin "29") (pinfunction "29_29") (pintype "unspecified+no_connect"))
    )
    (net (code "66") (name "unconnected-(H2-Pad30)") (class "Default")
      (node (ref "H2") (pin "30") (pinfunction "30_30") (pintype "unspecified+no_connect"))
    )
    (net (code "67") (name "unconnected-(H2-Pad31)") (class "Default")
      (node (ref "H2") (pin "31") (pinfunction "31_31") (pintype "unspecified+no_connect"))
    )
    (net (code "68") (name "unconnected-(H2-Pad32)") (class "Default")
      (node (ref "H2") (pin "32") (pinfunction "32_32") (pintype "unspecified+no_connect"))
    )
    (net (code "69") (name "unconnected-(H2-Pad33)") (class "Default")
      (node (ref "H2") (pin "33") (pinfunction "33_33") (pintype "unspecified+no_connect"))
    )
    (net (code "70") (name "unconnected-(H2-Pad34)") (class "Default")
      (node (ref "H2") (pin "34") (pinfunction "34_34") (pintype "unspecified+no_connect"))
    )
    (net (code "71") (name "unconnected-(H2-Pad35)") (class "Default")
      (node (ref "H2") (pin "35") (pinfunction "35_35") (pintype "unspecified+no_connect"))
    )
    (net (code "72") (name "unconnected-(H2-Pad36)") (class "Default")
      (node (ref "H2") (pin "36") (pinfunction "36_36") (pintype "unspecified+no_connect"))
    )
    (net (code "73") (name "unconnected-(H2-Pad37)") (class "Default")
      (node (ref "H2") (pin "37") (pinfunction "37_37") (pintype "unspecified+no_connect"))
    )
    (net (code "74") (name "unconnected-(H2-Pad38)") (class "Default")
      (node (ref "H2") (pin "38") (pinfunction "38_38") (pintype "unspecified+no_connect"))
    )
    (net (code "75") (name "unconnected-(H2-Pad39)") (class "Default")
      (node (ref "H2") (pin "39") (pinfunction "39_39") (pintype "unspecified+no_connect"))
    )
    (net (code "76") (name "unconnected-(H2-Pad40)") (class "Default")
      (node (ref "H2") (pin "40") (pinfunction "40_40") (pintype "unspecified+no_connect"))
    )
    (net (code "77") (name "unconnected-(U1-1Y0-Pad12)") (class "Default")
      (node (ref "U1") (pin "12") (pinfunction "1Y0_12") (pintype "unspecified+no_connect"))
    )
    (net (code "78") (name "unconnected-(U4-PA1-Pad15)") (class "Default")
      (node (ref "U4") (pin "15") (pinfunction "PA1_15") (pintype "unspecified+no_connect"))
    )
    (net (code "79") (name "unconnected-(U4-PA3-Pad17)") (class "Default")
      (node (ref "U4") (pin "17") (pinfunction "PA3_17") (pintype "unspecified+no_connect"))
    )
    (net (code "80") (name "unconnected-(U4-PA8-Pad41)") (class "Default")
      (node (ref "U4") (pin "41") (pinfunction "PA8_41") (pintype "unspecified+no_connect"))
    )
    (net (code "81") (name "unconnected-(U4-PA9-Pad42)") (class "Default")
      (node (ref "U4") (pin "42") (pinfunction "PA9_42") (pintype "unspecified+no_connect"))
    )
    (net (code "82") (name "unconnected-(U4-PA10-Pad43)") (class "Default")
      (node (ref "U4") (pin "43") (pinfunction "PA10_43") (pintype "unspecified+no_connect"))
    )
    (net (code "83") (name "unconnected-(U4-PA15-Pad50)") (class "Default")
      (node (ref "U4") (pin "50") (pinfunction "PA15_50") (pintype "unspecified+no_connect"))
    )
    (net (code "84") (name "unconnected-(U4-PB1-Pad27)") (class "Default")
      (node (ref "U4") (pin "27") (pinfunction "PB1_27") (pintype "unspecified+no_connect"))
    )
    (net (code "85") (name "unconnected-(U4-PB7-Pad59)") (class "Default")
      (node (ref "U4") (pin "59") (pinfunction "PB7_59") (pintype "unspecified+no_connect"))
    )
    (net (code "86") (name "unconnected-(U4-PB10-Pad29)") (class "Default")
      (node (ref "U4") (pin "29") (pinfunction "PB10_29") (pintype "unspecified+no_connect"))
    )
    (net (code "87") (name "unconnected-(U4-PC0-Pad8)") (class "Default")
      (node (ref "U4") (pin "8") (pinfunction "PC0_8") (pintype "unspecified+no_connect"))
    )
    (net (code "88") (name "unconnected-(U4-PC1-Pad9)") (class "Default")
      (node (ref "U4") (pin "9") (pinfunction "PC1_9") (pintype "unspecified+no_connect"))
    )
    (net (code "89") (name "unconnected-(U4-PC2-Pad10)") (class "Default")
      (node (ref "U4") (pin "10") (pinfunction "PC2_10") (pintype "unspecified+no_connect"))
    )
    (net (code "90") (name "unconnected-(U4-PC3-Pad11)") (class "Default")
      (node (ref "U4") (pin "11") (pinfunction "PC3_11") (pintype "unspecified+no_connect"))
    )
    (net (code "91") (name "unconnected-(U4-PC6-Pad37)") (class "Default")
      (node (ref "U4") (pin "37") (pinfunction "PC6_37") (pintype "unspecified+no_connect"))
    )
    (net (code "92") (name "unconnected-(U4-PC7-Pad38)") (class "Default")
      (node (ref "U4") (pin "38") (pinfunction "PC7_38") (pintype "unspecified+no_connect"))
    )
    (net (code "93") (name "unconnected-(U4-PC8-Pad39)") (class "Default")
      (node (ref "U4") (pin "39") (pinfunction "PC8_39") (pintype "unspecified+no_connect"))
    )
    (net (code "94") (name "unconnected-(U4-PC9-Pad40)") (class "Default")
      (node (ref "U4") (pin "40") (pinfunction "PC9_40") (pintype "unspecified+no_connect"))
    )
    (net (code "95") (name "unconnected-(U4-PC10-Pad51)") (class "Default")
      (node (ref "U4") (pin "51") (pinfunction "PC10_51") (pintype "unspecified+no_connect"))
    )
    (net (code "96") (name "unconnected-(U4-PC13-Pad2)") (class "Default")
      (node (ref "U4") (pin "2") (pinfunction "PC13_2") (pintype "unspecified+no_connect"))
    )
    (net (code "97") (name "unconnected-(U4-PC14-OSC32_IN-Pad3)") (class "Default")
      (node (ref "U4") (pin "3") (pinfunction "PC14-OSC32_IN_3") (pintype "unspecified+no_connect"))
    )
    (net (code "98") (name "unconnected-(U4-PC15-OSC32_OUT-Pad4)") (class "Default")
      (node (ref "U4") (pin "4") (pinfunction "PC15-OSC32_OUT_4") (pintype "unspecified+no_connect"))
    )
    (net (code "99") (name "unconnected-(U4-PD2-Pad54)") (class "Default")
      (node (ref "U4") (pin "54") (pinfunction "PD2_54") (pintype "unspecified+no_connect"))
    )
    (net (code "100") (name "unconnected-(U5-TAB-Pad4)") (class "Default")
      (node (ref "U5") (pin "4") (pinfunction "TAB_4") (pintype "unspecified+no_connect"))
    )
    (net (code "101") (name "unconnected-(USB1-ID-Pad4)") (class "Default")
      (node (ref "USB1") (pin "4") (pinfunction "ID_4") (pintype "input+no_connect"))
    )
  )
)
